# H2AR32.net
KiCad netlist of a schematic drawn in EAGLE
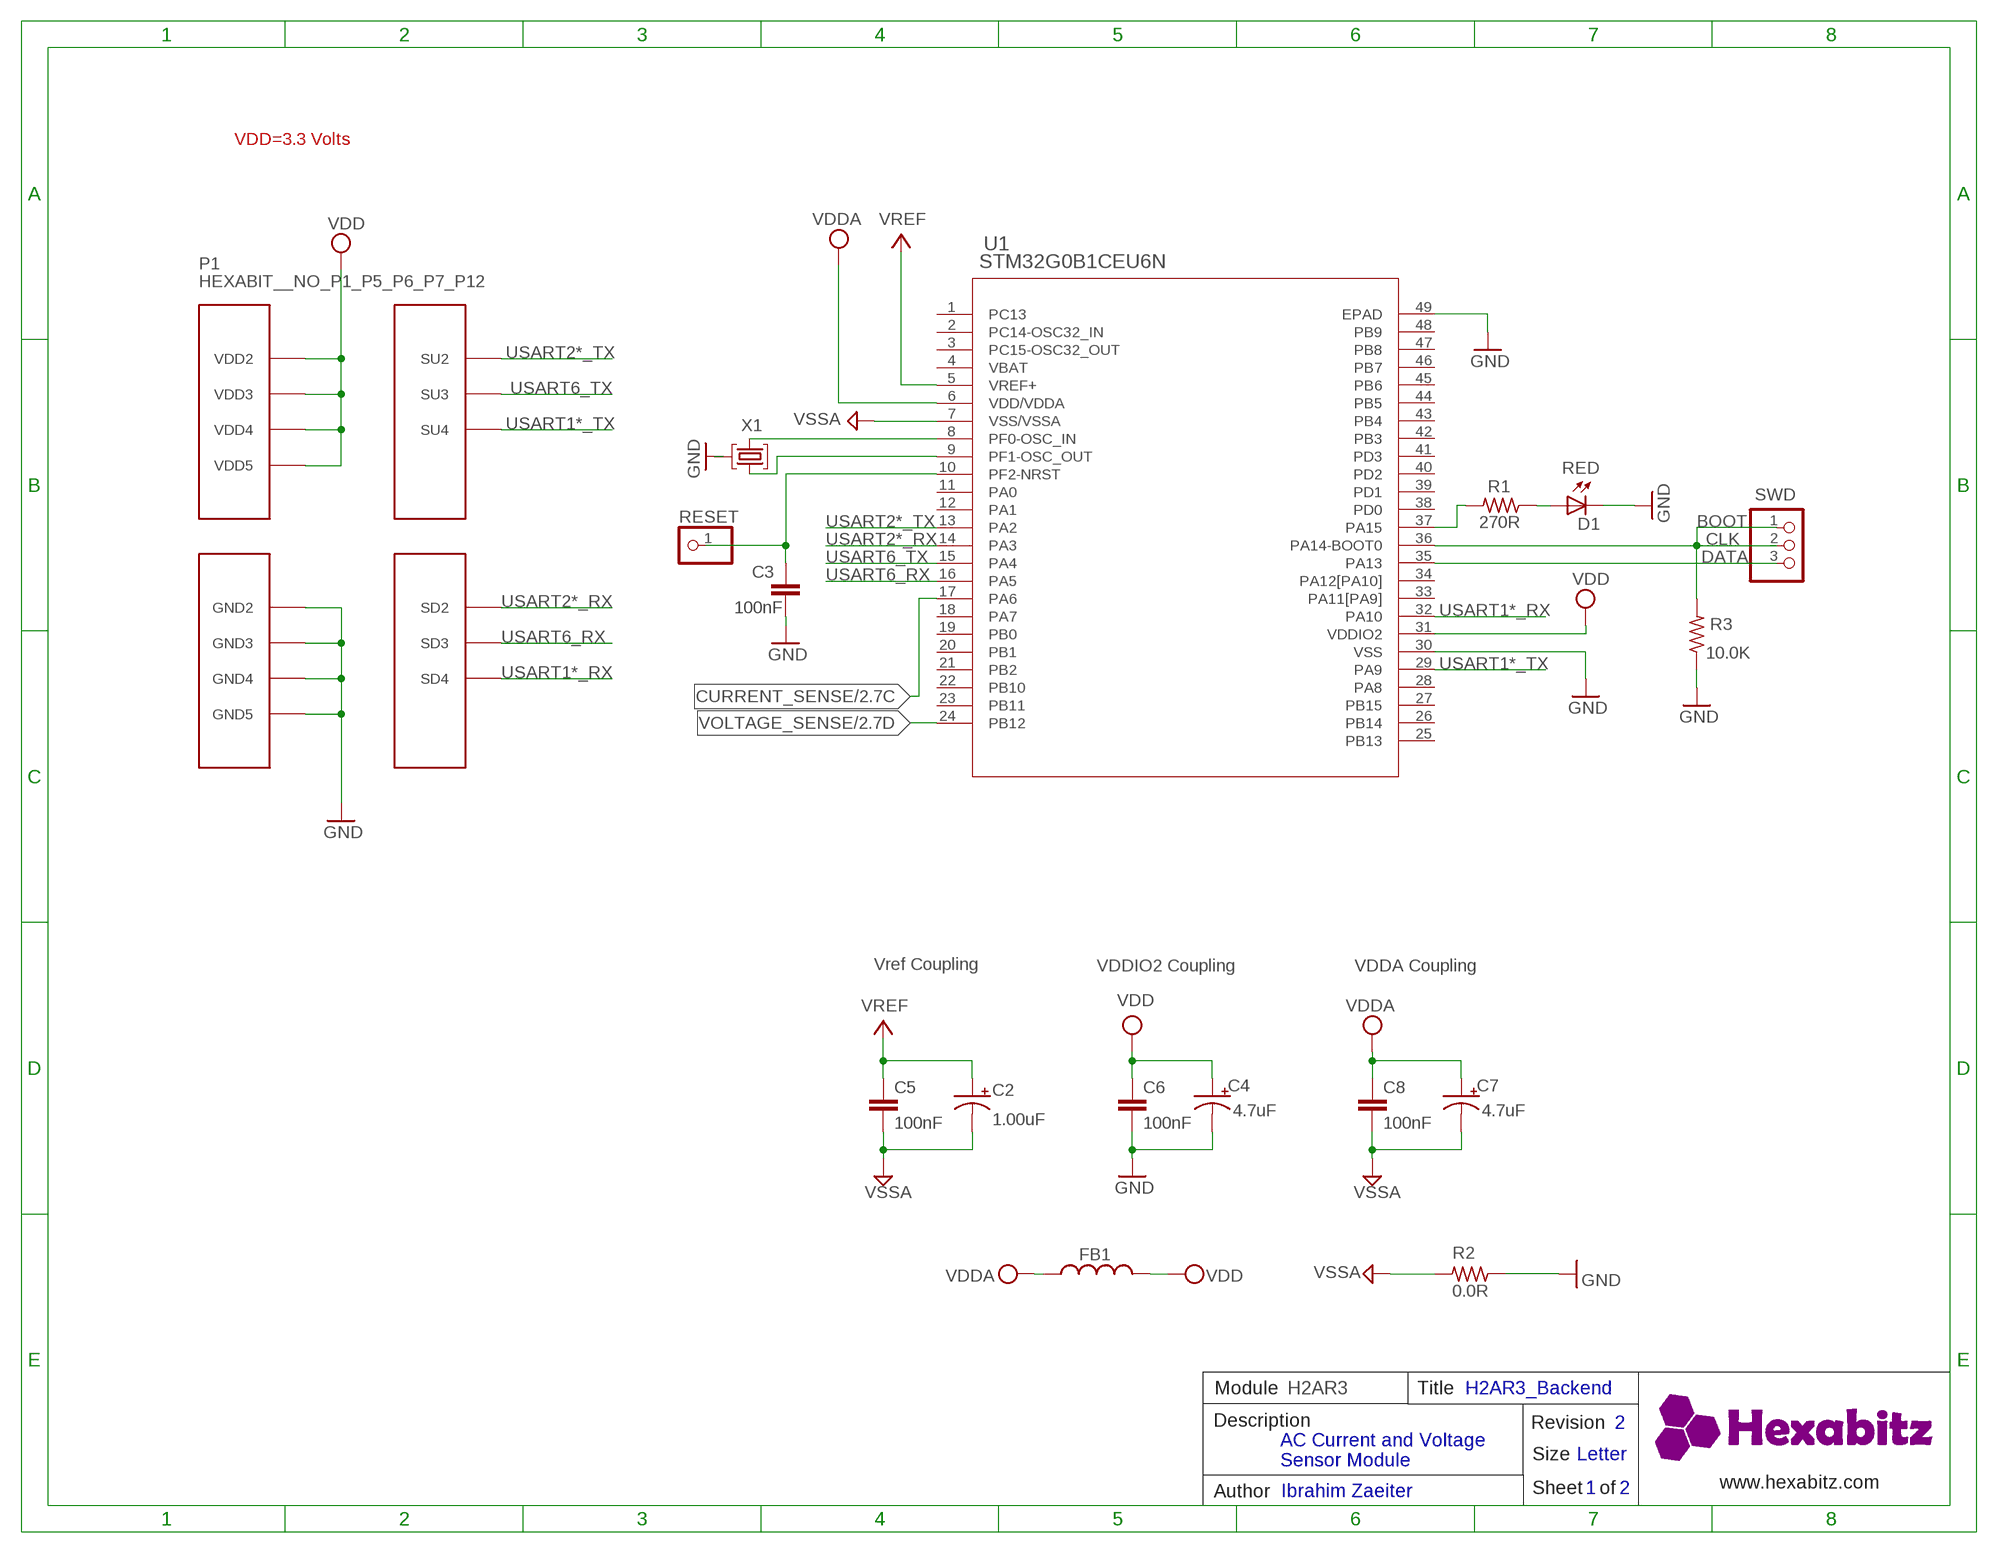
[diagram p0: schematic, sheet 1]
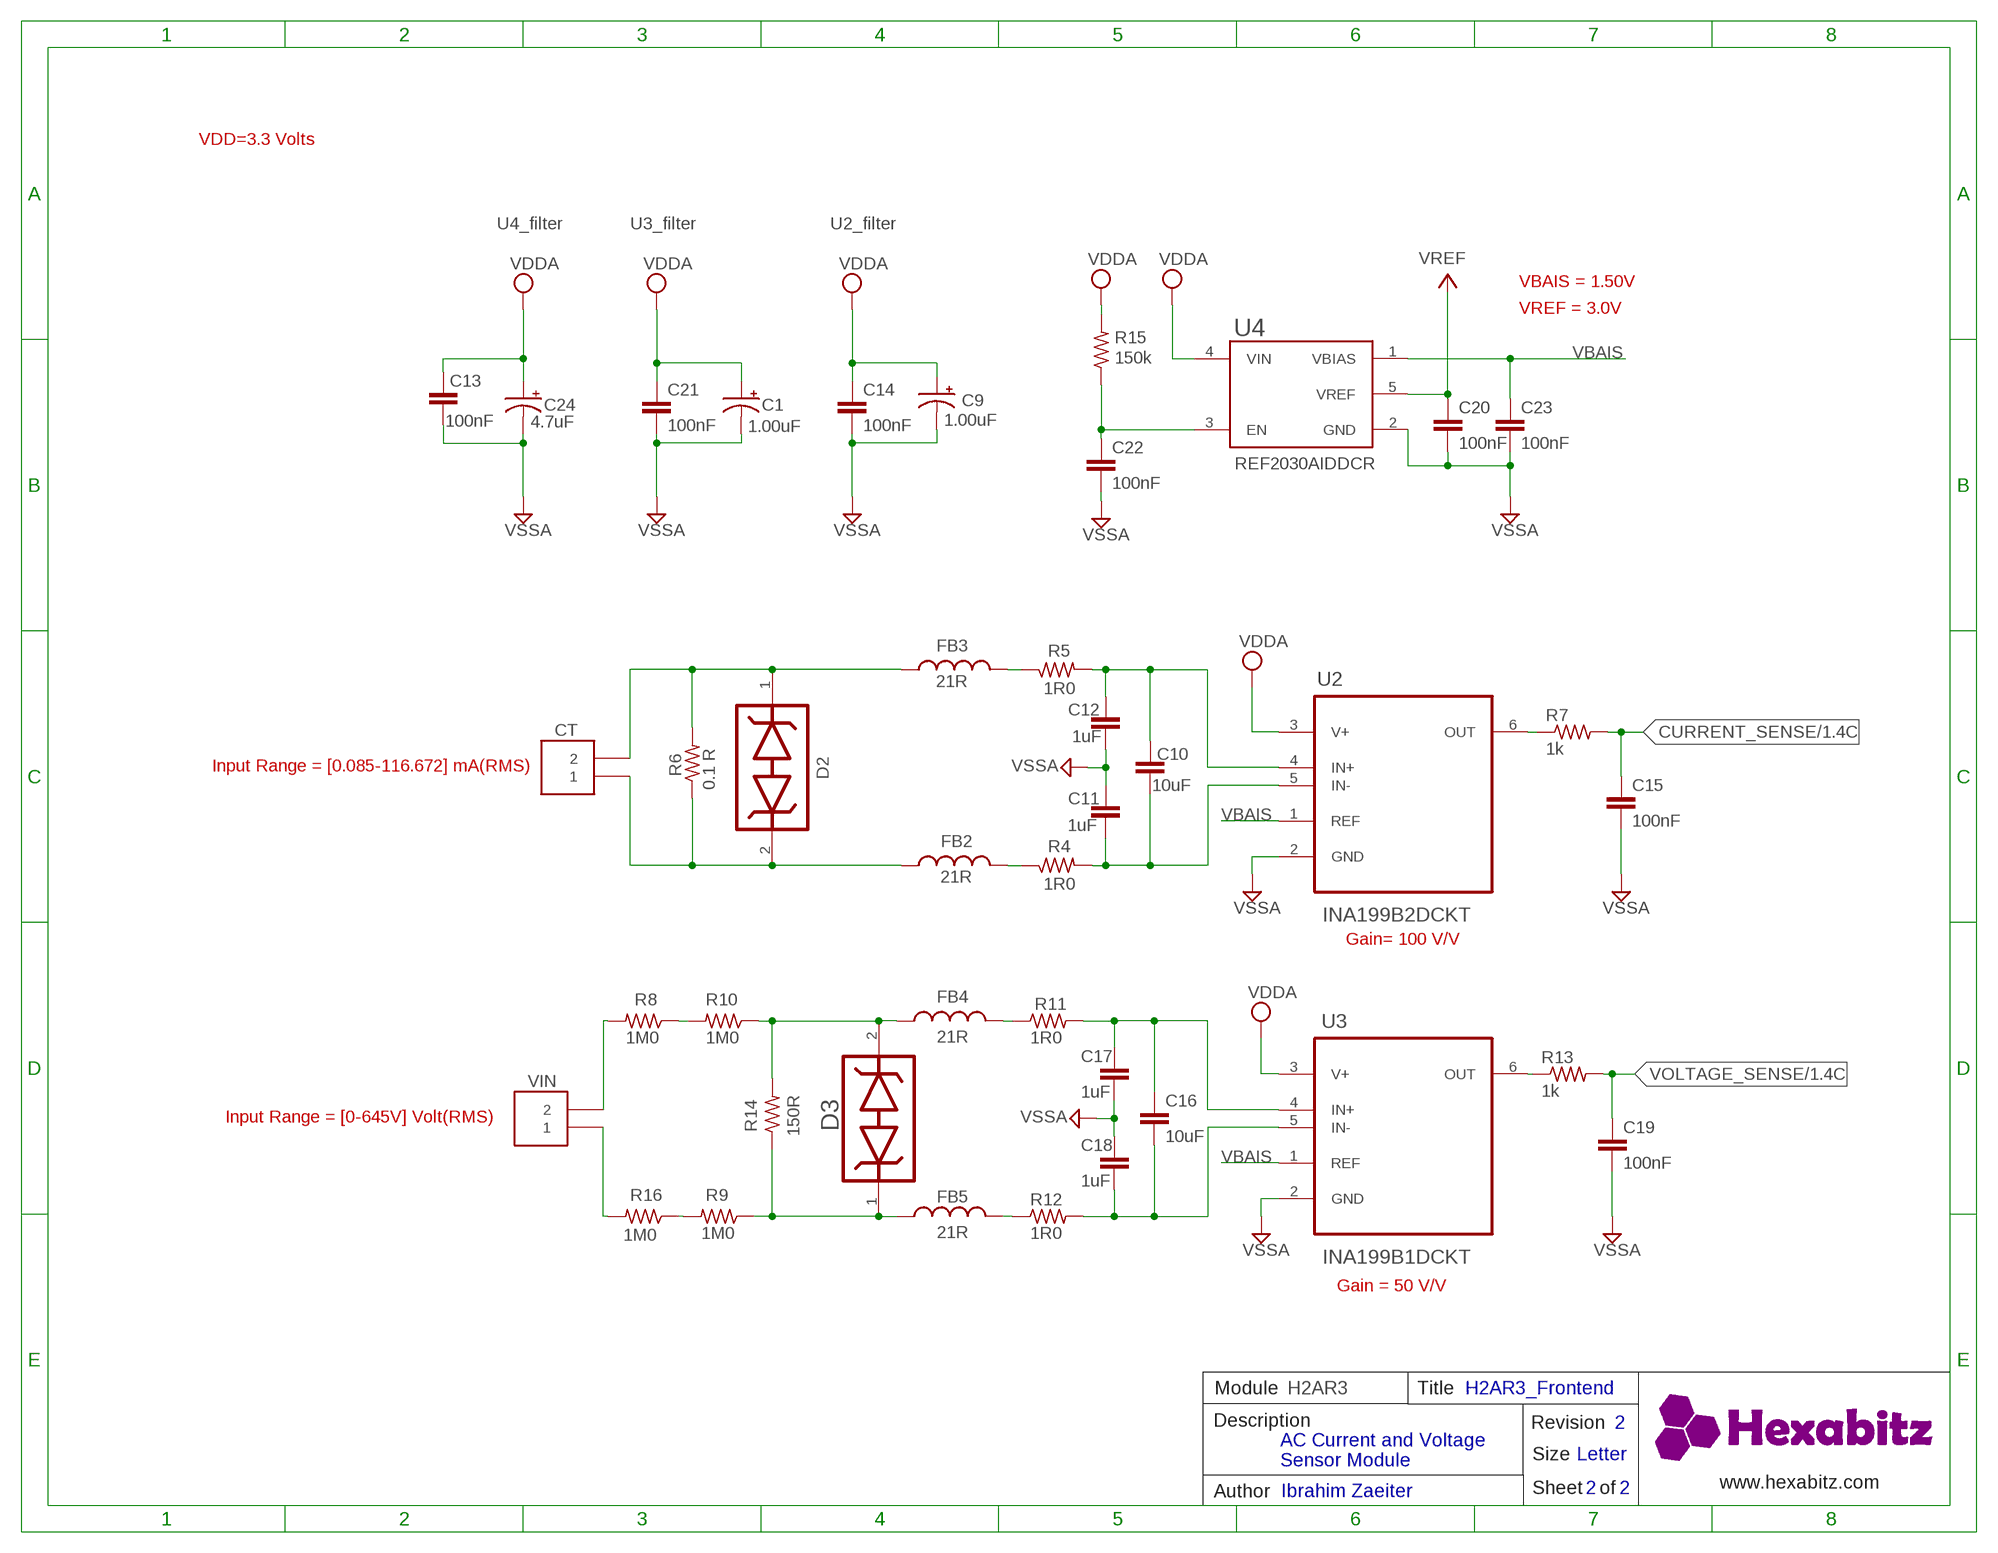
[diagram p1: schematic, sheet 2]

(export (version "E")
  (design (tool "Eeschema 10.0.6"))
  (components
    (comp (ref "C1")
      (value "1.00uF")
      (footprint "eagle-import:C-0805-POL")
      (fields
        (field (name "CAPACITANCE") "1.00uF")
        (field (name "MFN") "Yageo")
        (field (name "MPN") "CC0805KKX7R7BB105")
        (field (name "OCTOPART_URL") "https://octopart.com/cc0805kkx7r7bb105-yageo-8376555?r=sp&s=YKl1wwtkROau_X5nniH2ig")
        (field (name "TOLERANCE") "10%")
        (field (name "VOLTAGE_RATING") "16V")
      )
      (libsource (lib "eagle-import") (part "C-0805-POL"))
    )
    (comp (ref "C9")
      (value "1.00uF")
      (footprint "eagle-import:C-0805-POL")
      (fields
        (field (name "CAPACITANCE") "1.00uF")
        (field (name "MFN") "Yageo")
        (field (name "MPN") "CC0805KKX7R7BB105")
        (field (name "OCTOPART_URL") "https://octopart.com/cc0805kkx7r7bb105-yageo-8376555?r=sp&s=YKl1wwtkROau_X5nniH2ig")
        (field (name "TOLERANCE") "10%")
        (field (name "VOLTAGE_RATING") "16V")
      )
      (libsource (lib "eagle-import") (part "C-0805-POL"))
    )
    (comp (ref "C10")
      (value "10uF")
      (footprint "eagle-import:C-0603")
      (fields
        (field (name "CAPACITANCE") "10uF")
        (field (name "MFN") "KEMET")
        (field (name "MPN") "C0603C106M9PACTU")
        (field (name "OCTOPART_URL") "https://octopart.com/c0603c106m9pactu-kemet-8375727?r=sp")
        (field (name "VOLTAGE_RATING") "6.3v")
      )
      (libsource (lib "eagle-import") (part "C-0603"))
    )
    (comp (ref "C11")
      (value "1uF")
      (footprint "eagle-import:C-0603")
      (fields
        (field (name "CAPACITANCE") "1uF")
        (field (name "MFN") "KEMET")
        (field (name "MPN") "C0603C105K8RACTU")
        (field (name "OCTOPART_URL") "https://octopart.com/c0603c105k8ractu-kemet-12595642?r=sp")
        (field (name "TOLERANCE") "10%")
        (field (name "VOLTAGE_RATING") "10v")
      )
      (libsource (lib "eagle-import") (part "C-0603"))
    )
    (comp (ref "C12")
      (value "1uF")
      (footprint "eagle-import:C-0603")
      (fields
        (field (name "CAPACITANCE") "1uF")
        (field (name "MFN") "KEMET")
        (field (name "MPN") "C0603C105K8RACTU")
        (field (name "OCTOPART_URL") "https://octopart.com/c0603c105k8ractu-kemet-12595642?r=sp")
        (field (name "TOLERANCE") "10%")
        (field (name "VOLTAGE_RATING") "10v")
      )
      (libsource (lib "eagle-import") (part "C-0603"))
    )
    (comp (ref "C13")
      (value "100nF")
      (footprint "eagle-import:C-0603")
      (fields
        (field (name "CAPACITANCE") "100nF")
        (field (name "MFN") "KEMET")
        (field (name "MPN") "C0603C104K8RACTU")
        (field (name "OCTOPART_URL") "https://octopart.com/c0603c104k8ractu-kemet-145075?r=sp&s=9bS9ASSwSEqMCE9KBEQZ0g")
        (field (name "TOLERANCE") "10%")
        (field (name "VOLTAGE_RATING") "10V")
      )
      (libsource (lib "eagle-import") (part "C-0603"))
    )
    (comp (ref "C14")
      (value "100nF")
      (footprint "eagle-import:C-0603")
      (fields
        (field (name "CAPACITANCE") "100nF")
        (field (name "MFN") "KEMET")
        (field (name "MPN") "C0603C104K8RACTU")
        (field (name "OCTOPART_URL") "https://octopart.com/c0603c104k8ractu-kemet-145075?r=sp&s=9bS9ASSwSEqMCE9KBEQZ0g")
        (field (name "TOLERANCE") "10%")
        (field (name "VOLTAGE_RATING") "10V")
      )
      (libsource (lib "eagle-import") (part "C-0603"))
    )
    (comp (ref "C15")
      (value "100nF")
      (footprint "eagle-import:C-0603")
      (fields
        (field (name "CAPACITANCE") "100nF")
        (field (name "MFN") "KEMET")
        (field (name "MPN") "C0603C104K8RACTU")
        (field (name "OCTOPART_URL") "https://octopart.com/c0603c104k8ractu-kemet-145075?r=sp&s=9bS9ASSwSEqMCE9KBEQZ0g")
        (field (name "TOLERANCE") "10%")
        (field (name "VOLTAGE_RATING") "10V")
      )
      (libsource (lib "eagle-import") (part "C-0603"))
    )
    (comp (ref "C16")
      (value "10uF")
      (footprint "eagle-import:C-0603")
      (fields
        (field (name "CAPACITANCE") "10uF")
        (field (name "MFN") "KEMET")
        (field (name "MPN") "C0603C106M9PACTU")
        (field (name "OCTOPART_URL") "https://octopart.com/c0603c106m9pactu-kemet-8375727?r=sp")
        (field (name "TOLERANCE") "20%")
        (field (name "VOLTAGE_RATING") "6.3V")
      )
      (libsource (lib "eagle-import") (part "C-0603"))
    )
    (comp (ref "C17")
      (value "1uF")
      (footprint "eagle-import:C-0603")
      (fields
        (field (name "CAPACITANCE") "1uF")
        (field (name "MFN") "KEMET")
        (field (name "MPN") "C0603C105K8RACTU")
        (field (name "OCTOPART_URL") "https://octopart.com/c0603c105k8ractu-kemet-12595642?r=sp")
        (field (name "TOLERANCE") "10%")
        (field (name "VOLTAGE_RATING") "10v")
      )
      (libsource (lib "eagle-import") (part "C-0603"))
    )
    (comp (ref "C18")
      (value "1uF")
      (footprint "eagle-import:C-0603")
      (fields
        (field (name "CAPACITANCE") "1uF")
        (field (name "MFN") "KEMET")
        (field (name "MPN") "C0603C105K8RACTU")
        (field (name "OCTOPART_URL") "https://octopart.com/c0603c105k8ractu-kemet-12595642?r=sp")
        (field (name "TOLERANCE") "10%")
        (field (name "VOLTAGE_RATING") "10v")
      )
      (libsource (lib "eagle-import") (part "C-0603"))
    )
    (comp (ref "C19")
      (value "100nF")
      (footprint "eagle-import:C-0603")
      (fields
        (field (name "CAPACITANCE") "100nF")
        (field (name "MFN") "KEMET")
        (field (name "MPN") "C0603C104K8RACTU")
        (field (name "OCTOPART_URL") "https://octopart.com/c0603c104k8ractu-kemet-145075?r=sp&s=9bS9ASSwSEqMCE9KBEQZ0g")
        (field (name "TOLERANCE") "10%")
        (field (name "VOLTAGE_RATING") "10V")
      )
      (libsource (lib "eagle-import") (part "C-0603"))
    )
    (comp (ref "C20")
      (value "100nF")
      (footprint "eagle-import:C-0603")
      (fields
        (field (name "CAPACITANCE") "100nF")
        (field (name "MFN") "KEMET")
        (field (name "MPN") "C0603C104K8RACTU")
        (field (name "OCTOPART_URL") "https://octopart.com/c0603c104k8ractu-kemet-145075?r=sp&s=9bS9ASSwSEqMCE9KBEQZ0g")
        (field (name "TOLERANCE") "10%")
        (field (name "VOLTAGE_RATING") "10V")
      )
      (libsource (lib "eagle-import") (part "C-0603"))
    )
    (comp (ref "C21")
      (value "100nF")
      (footprint "eagle-import:C-0603")
      (fields
        (field (name "CAPACITANCE") "100nF")
        (field (name "MFN") "KEMET")
        (field (name "MPN") "C0603C104K8RACTU")
        (field (name "OCTOPART_URL") "https://octopart.com/c0603c104k8ractu-kemet-145075?r=sp&s=9bS9ASSwSEqMCE9KBEQZ0g")
        (field (name "TOLERANCE") "10%")
        (field (name "VOLTAGE_RATING") "10V")
      )
      (libsource (lib "eagle-import") (part "C-0603"))
    )
    (comp (ref "C22")
      (value "100nF")
      (footprint "eagle-import:C-0603")
      (fields
        (field (name "CAPACITANCE") "100nF")
        (field (name "MFN") "KEMET")
        (field (name "MPN") "C0603C104K8RACTU")
        (field (name "OCTOPART_URL") "https://octopart.com/c0603c104k8ractu-kemet-145075?r=sp&s=9bS9ASSwSEqMCE9KBEQZ0g")
        (field (name "TOLERANCE") "10%")
        (field (name "VOLTAGE_RATING") "10V")
      )
      (libsource (lib "eagle-import") (part "C-0603"))
    )
    (comp (ref "C23")
      (value "100nF")
      (footprint "eagle-import:C-0603")
      (fields
        (field (name "CAPACITANCE") "100nF")
        (field (name "MFN") "KEMET")
        (field (name "MPN") "C0603C104K8RACTU")
        (field (name "OCTOPART_URL") "https://octopart.com/c0603c104k8ractu-kemet-145075?r=sp&s=9bS9ASSwSEqMCE9KBEQZ0g")
        (field (name "TOLERANCE") "10%")
        (field (name "VOLTAGE_RATING") "10V")
      )
      (libsource (lib "eagle-import") (part "C-0603"))
    )
    (comp (ref "C24")
      (value "4.7uF")
      (footprint "eagle-import:C-0805-POL")
      (fields
        (field (name "CAPACITANCE") "4.7uF")
        (field (name "MFN") "Murata")
        (field (name "MPN") "GRM21BC81E475KA12L")
        (field (name "OCTOPART_URL") "https://octopart.com/grm21bc81e475ka12l-murata-10331911?r=sp&s=RY3qZSD8T6mG6TC9CHI5qQ")
        (field (name "TOLERANCE") "10%")
        (field (name "VOLTAGE_RATING") "25V")
      )
      (libsource (lib "eagle-import") (part "C-0805-POL"))
    )
    (comp (ref "CT")
      (value "1546111-2")
      (footprint "eagle-import:1546111-2")
      (libsource (lib "eagle-import") (part "1546111-2"))
    )
    (comp (ref "D2")
      (value "BOURNS_CDSOD323-T03SCBOURNS_CDSOD323-T03SC_0_0")
      (footprint "eagle-import:BOURNS_CDSOD323-T03SC_0")
      (fields (field (name "MPN") "CDSOD323-T03SC"))
      (libsource (lib "eagle-import") (part "BOURNS_CDSOD323-T03SCBOURNS_CDSOD323-T03SC_0_0"))
    )
    (comp (ref "D3")
      (value "BOURNS_CDSOD323-T03SCBOURNS_CDSOD323-T03SC_0_0")
      (footprint "eagle-import:BOURNS_CDSOD323-T03SC_0")
      (fields (field (name "MPN") "CDSOD323-T03SC"))
      (libsource (lib "eagle-import") (part "BOURNS_CDSOD323-T03SCBOURNS_CDSOD323-T03SC_0_0"))
    )
    (comp (ref "FB2")
      (value "21R")
      (footprint "eagle-import:FB-0805")
      (fields
        (field (name "MFN") "Taiyo Yuden")
        (field (name "MPN") "FBMJ2125HM210NT")
        (field (name "OCTOPART_URL") "https://octopart.com/fbmj2125hm210nt-taiyo+yuden-368424?r=sp")
      )
      (libsource (lib "eagle-import") (part "FB-0805"))
    )
    (comp (ref "FB3")
      (value "21R")
      (footprint "eagle-import:FB-0805")
      (fields
        (field (name "MFN") "Taiyo Yuden")
        (field (name "MPN") "FBMJ2125HM210NT")
        (field (name "OCTOPART_URL") "https://octopart.com/fbmj2125hm210nt-taiyo+yuden-368424?r=sp")
      )
      (libsource (lib "eagle-import") (part "FB-0805"))
    )
    (comp (ref "FB4")
      (value "21R")
      (footprint "eagle-import:FB-0805")
      (fields
        (field (name "MFN") "Taiyo Yuden")
        (field (name "MPN") "FBMJ2125HM210NT")
        (field (name "OCTOPART_URL") "https://octopart.com/fbmj2125hm210nt-taiyo+yuden-368424?r=sp")
      )
      (libsource (lib "eagle-import") (part "FB-0805"))
    )
    (comp (ref "FB5")
      (value "21R")
      (footprint "eagle-import:FB-0805")
      (fields
        (field (name "MFN") "Taiyo Yuden")
        (field (name "MPN") "FBMJ2125HM210NT")
        (field (name "OCTOPART_URL") "https://octopart.com/fbmj2125hm210nt-taiyo+yuden-368424?r=sp")
      )
      (libsource (lib "eagle-import") (part "FB-0805"))
    )
    (comp (ref "R4")
      (value "1R0")
      (footprint "eagle-import:R-0603")
      (fields
        (field (name "MFN") "Vishay")
        (field (name "MPN") "CRCW06031R00FKEA")
        (field (name "OCTOPART_URL") "https://octopart.com/crcw06031r00fkea-vishay-39713722?r=sp&s=biXSlGylTBiwPOCcABx_kA")
        (field (name "RESISTANCE") "1")
        (field (name "TOLERANCE") "1%")
      )
      (libsource (lib "eagle-import") (part "R-0603"))
    )
    (comp (ref "R5")
      (value "1R0")
      (footprint "eagle-import:R-0603")
      (fields
        (field (name "MFN") "Vishay")
        (field (name "MPN") "CRCW06031R00FKEA")
        (field (name "OCTOPART_URL") "https://octopart.com/crcw06031r00fkea-vishay-39713722?r=sp&s=biXSlGylTBiwPOCcABx_kA")
        (field (name "RESISTANCE") "1")
        (field (name "TOLERANCE") "1%")
      )
      (libsource (lib "eagle-import") (part "R-0603"))
    )
    (comp (ref "R6")
      (value "0.1 R")
      (footprint "eagle-import:R2512")
      (libsource (lib "eagle-import") (part "R-US_R2512"))
    )
    (comp (ref "R7")
      (value "1k")
      (footprint "eagle-import:R-0603")
      (fields
        (field (name "MFN") "Yageo")
        (field (name "MPN") "RC0603JR-071KL")
        (field (name "OCTOPART_URL") "https://octopart.com/rc0603jr-071kl-yageo-55402888?r=sp")
        (field (name "RESISTANCE") "1K")
        (field (name "TOLERANCE") "5%")
      )
      (libsource (lib "eagle-import") (part "R-0603"))
    )
    (comp (ref "R8")
      (value "1M0")
      (footprint "eagle-import:R1206")
      (fields
        (field (name "MPN") "RNCF2512BTE1M10")
        (field (name "MFN") "Yageo")
        (field (name "MPN_1") "RT1206BRD071ML")
        (field (name "OCTOPART_URL") "https://octopart.com/rt1206brd071ml-yageo-1262221?r=sp")
      )
      (libsource (lib "eagle-import") (part "R_1206R1206"))
    )
    (comp (ref "R9")
      (value "1M0")
      (footprint "eagle-import:R1206")
      (fields
        (field (name "MPN") "RNCF2512BTE1M10")
        (field (name "MFN") "Yageo")
        (field (name "MPN_1") "RT1206BRD071ML")
        (field (name "OCTOPART_URL") "https://octopart.com/rt1206brd071ml-yageo-1262221?r=sp")
      )
      (libsource (lib "eagle-import") (part "R_1206R1206"))
    )
    (comp (ref "R10")
      (value "1M0")
      (footprint "eagle-import:R1206")
      (fields
        (field (name "MPN") "RNCF2512BTE1M10")
        (field (name "MFN") "Yageo")
        (field (name "MPN_1") "RT1206BRD071ML")
        (field (name "OCTOPART_URL") "https://octopart.com/rt1206brd071ml-yageo-1262221?r=sp")
      )
      (libsource (lib "eagle-import") (part "R_1206R1206"))
    )
    (comp (ref "R11")
      (value "1R0")
      (footprint "eagle-import:R-0603")
      (fields
        (field (name "MFN") "Vishay")
        (field (name "MPN") "CRCW06031R00FKEA")
        (field (name "OCTOPART_URL") "https://octopart.com/crcw06031r00fkea-vishay-39713722?r=sp&s=biXSlGylTBiwPOCcABx_kA")
        (field (name "RESISTANCE") "1")
        (field (name "TOLERANCE") "1%")
      )
      (libsource (lib "eagle-import") (part "R-0603"))
    )
    (comp (ref "R12")
      (value "1R0")
      (footprint "eagle-import:R-0603")
      (fields
        (field (name "MFN") "Vishay")
        (field (name "MPN") "CRCW06031R00FKEA")
        (field (name "OCTOPART_URL") "https://octopart.com/crcw06031r00fkea-vishay-39713722?r=sp&s=biXSlGylTBiwPOCcABx_kA")
        (field (name "RESISTANCE") "1")
        (field (name "TOLERANCE") "1%")
      )
      (libsource (lib "eagle-import") (part "R-0603"))
    )
    (comp (ref "R13")
      (value "1k")
      (footprint "eagle-import:R-0603")
      (fields
        (field (name "MFN") "Yageo")
        (field (name "MPN") "RC0603JR-071KL")
        (field (name "OCTOPART_URL") "https://octopart.com/rc0603jr-071kl-yageo-55402888?r=sp")
        (field (name "RESISTANCE") "1K")
        (field (name "TOLERANCE") "5%")
      )
      (libsource (lib "eagle-import") (part "R-0603"))
    )
    (comp (ref "R14")
      (value "150R")
      (footprint "eagle-import:R1206")
      (fields
        (field (name "MPN") "RNCF2512BTE1M10")
        (field (name "MFN") "Panasonic")
        (field (name "MPN_1") "ERA-8AEB151V")
        (field (name "OCTOPART_URL") "https://octopart.com/era-8aeb151v-panasonic-55477439?r=sp")
      )
      (libsource (lib "eagle-import") (part "R_1206R1206"))
    )
    (comp (ref "R15")
      (value "150k")
      (footprint "eagle-import:R-0603")
      (fields
        (field (name "MFN") "Vishay")
        (field (name "MPN") "CRCW0603150KFKEA")
        (field (name "OCTOPART_URL") "https://octopart.com/crcw0603150kfkea-vishay-39455816?r=sp")
        (field (name "RESISTANCE") "150K")
        (field (name "TOLERANCE") "1%")
      )
      (libsource (lib "eagle-import") (part "R-0603"))
    )
    (comp (ref "R16")
      (value "1M0")
      (footprint "eagle-import:R1206")
      (fields
        (field (name "MPN") "RNCF2512BTE1M10")
        (field (name "MFN") "Yageo")
        (field (name "MPN_1") "RT1206BRD071ML")
        (field (name "OCTOPART_URL") "https://octopart.com/rt1206brd071ml-yageo-1262221?r=sp")
      )
      (libsource (lib "eagle-import") (part "R_1206R1206"))
    )
    (comp (ref "U2")
      (value "INA199B2DCKT")
      (footprint "eagle-import:SOT65P210X110-6N")
      (libsource (lib "eagle-import") (part "INA199B2DCKT"))
    )
    (comp (ref "U3")
      (value "INA199B1DCKT")
      (footprint "eagle-import:SOT65P210X110-6N")
      (libsource (lib "eagle-import") (part "INA199B1DCKT"))
    )
    (comp (ref "U4")
      (value "TEXAS_INSTRUMENTS_REF2033AIDDCRTEXAS_INSTRUMENTS_REF2033AIDDCR_0_2")
      (footprint "eagle-import:TEXAS_INSTRUMENTS_REF2033AIDDCR_2")
      (fields (field (name "MPN") "REF2033AIDDCR") (field (name "MPN_1") "REF2030AIDDCR"))
      (libsource (lib "eagle-import") (part "TEXAS_INSTRUMENTS_REF2033AIDDCRTEXAS_INSTRUMENTS_REF2033AIDDCR_0_2"))
    )
    (comp (ref "VIN")
      (value "1546111-2")
      (footprint "eagle-import:1546111-2")
      (libsource (lib "eagle-import") (part "1546111-2"))
    )
    (comp (ref "C2")
      (value "1.00uF")
      (footprint "eagle-import:C-0805-POL")
      (fields
        (field (name "CAPACITANCE") "1.00uF")
        (field (name "MFN") "Yageo")
        (field (name "MPN") "CC0805KKX7R7BB105")
        (field (name "OCTOPART_URL") "https://octopart.com/cc0805kkx7r7bb105-yageo-8376555?r=sp&s=YKl1wwtkROau_X5nniH2ig")
        (field (name "TOLERANCE") "10%")
        (field (name "VOLTAGE_RATING") "16V")
      )
      (libsource (lib "eagle-import") (part "C-0805-POL"))
    )
    (comp (ref "C3")
      (value "100nF")
      (footprint "eagle-import:C-0603")
      (fields
        (field (name "CAPACITANCE") "100nF")
        (field (name "MFN") "KEMET")
        (field (name "MPN") "C0603C104K8RACTU")
        (field (name "OCTOPART_URL") "https://octopart.com/c0603c104k8ractu-kemet-145075?r=sp&s=9bS9ASSwSEqMCE9KBEQZ0g")
        (field (name "TOLERANCE") "10%")
        (field (name "VOLTAGE_RATING") "10V")
      )
      (libsource (lib "eagle-import") (part "C-0603"))
    )
    (comp (ref "C4")
      (value "4.7uF")
      (footprint "eagle-import:C-0805-POL")
      (fields
        (field (name "CAPACITANCE") "4.7uF")
        (field (name "MFN") "Murata")
        (field (name "MPN") "GRM21BC81E475KA12L")
        (field (name "OCTOPART_URL") "https://octopart.com/grm21bc81e475ka12l-murata-10331911?r=sp&s=RY3qZSD8T6mG6TC9CHI5qQ")
        (field (name "TOLERANCE") "10%")
        (field (name "VOLTAGE_RATING") "25V")
      )
      (libsource (lib "eagle-import") (part "C-0805-POL"))
    )
    (comp (ref "C5")
      (value "100nF")
      (footprint "eagle-import:C-0603")
      (fields
        (field (name "CAPACITANCE") "100nF")
        (field (name "MFN") "KEMET")
        (field (name "MPN") "C0603C104K8RACTU")
        (field (name "OCTOPART_URL") "https://octopart.com/c0603c104k8ractu-kemet-145075?r=sp&s=9bS9ASSwSEqMCE9KBEQZ0g")
        (field (name "TOLERANCE") "10%")
        (field (name "VOLTAGE_RATING") "10V")
      )
      (libsource (lib "eagle-import") (part "C-0603"))
    )
    (comp (ref "C6")
      (value "100nF")
      (footprint "eagle-import:C-0603")
      (fields
        (field (name "CAPACITANCE") "100nF")
        (field (name "MFN") "KEMET")
        (field (name "MPN") "C0603C104K8RACTU")
        (field (name "OCTOPART_URL") "https://octopart.com/c0603c104k8ractu-kemet-145075?r=sp&s=9bS9ASSwSEqMCE9KBEQZ0g")
        (field (name "TOLERANCE") "10%")
        (field (name "VOLTAGE_RATING") "10V")
      )
      (libsource (lib "eagle-import") (part "C-0603"))
    )
    (comp (ref "C7")
      (value "4.7uF")
      (footprint "eagle-import:C-0805-POL")
      (fields
        (field (name "CAPACITANCE") "4.7uF")
        (field (name "MFN") "Murata")
        (field (name "MPN") "GRM21BC81E475KA12L")
        (field (name "OCTOPART_URL") "https://octopart.com/grm21bc81e475ka12l-murata-10331911?r=sp&s=RY3qZSD8T6mG6TC9CHI5qQ")
        (field (name "TOLERANCE") "10%")
        (field (name "VOLTAGE_RATING") "25V")
      )
      (libsource (lib "eagle-import") (part "C-0805-POL"))
    )
    (comp (ref "C8")
      (value "100nF")
      (footprint "eagle-import:C-0603")
      (fields
        (field (name "CAPACITANCE") "100nF")
        (field (name "MFN") "KEMET")
        (field (name "MPN") "C0603C104K8RACTU")
        (field (name "OCTOPART_URL") "https://octopart.com/c0603c104k8ractu-kemet-145075?r=sp&s=9bS9ASSwSEqMCE9KBEQZ0g")
        (field (name "TOLERANCE") "10%")
        (field (name "VOLTAGE_RATING") "10")
      )
      (libsource (lib "eagle-import") (part "C-0603"))
    )
    (comp (ref "D1")
      (value "RED")
      (footprint "eagle-import:VLMS1300-GS08")
      (fields
        (field (name "MPN") "VLMS1300-GS08")
        (field (name "MFN") "Vishay")
        (field (name "MPN_1") "VLMS1300-GS08")
        (field (name "OCTOPART_URL") "https://octopart.com/vlms1300-gs08-vishay-21709201?r=sp&s=_gcP4_q8T1SC6PJQPTQ9yA")
      )
      (libsource (lib "eagle-import") (part "VLMS1300-GS08"))
    )
    (comp (ref "FB1")
      (value "FB-TDK_MMZ1608Y300B")
      (footprint "eagle-import:FB-TDK_MMZ1608Y300B")
      (fields
        (field (name "MFN") "TDK ")
        (field (name "MPN") "MMZ1608Y300B")
        (field (name "OCTOPART_URL") "https://octopart.com/mmz1608y300b-tdk-368280?r=sp&s=cd9_2ZEqQ9q9UNBuQgHAiA")
      )
      (libsource (lib "eagle-import") (part "FB-TDK_MMZ1608Y300B"))
    )
    (comp (ref "P1")
      (value "HEXABIT__NO_P1_P5_P6_P7_P12")
      (footprint "eagle-import:HEXABIT_17.32_NO_P1_P6_P5_P7_P12")
      (libsource (lib "eagle-import") (part "HEXABIT_?_NO_P1_P5_P6_P7_P12"))
    )
    (comp (ref "R1")
      (value "270R")
      (footprint "eagle-import:R-0603")
      (fields
        (field (name "MFN") "Yageo")
        (field (name "MPN") "RC0603FR-07270RL")
        (field (name "OCTOPART_URL") "https://octopart.com/search?q=RC0603FR-07270RL&start=0")
        (field (name "RESISTANCE") "270.0 Ohm")
        (field (name "TOLERANCE") "5%")
      )
      (libsource (lib "eagle-import") (part "R-0603"))
    )
    (comp (ref "R2")
      (value "0.0R")
      (footprint "eagle-import:R-0603")
      (fields
        (field (name "MFN") "Yageo")
        (field (name "MPN") "RC0603JR-070RL")
        (field (name "OCTOPART_URL") "https://octopart.com/rc0603jr-070rl-yageo-1241539?r=sp&s=X2NteqRjRNWrnx42Y0aliA")
        (field (name "RESISTANCE") "0.0 Ohm")
      )
      (libsource (lib "eagle-import") (part "R-0603"))
    )
    (comp (ref "R3")
      (value "10.0K")
      (footprint "eagle-import:R-0603")
      (fields
        (field (name "MFN") "Yageo")
        (field (name "MPN") "RC0603JR-0710KL")
        (field (name "OCTOPART_URL") "https://octopart.com/search?q=RC0603JR-0710KL&start=0")
        (field (name "RESISTANCE") "10.0K Ohm")
        (field (name "TOLERANCE") "5%")
      )
      (libsource (lib "eagle-import") (part "R-0603"))
    )
    (comp (ref "RESET")
      (value "R")
      (footprint "eagle-import:1X01")
      (fields (field (name "MPN") "87227-1"))
      (libsource (lib "eagle-import") (part "PINHD-1X1"))
    )
    (comp (ref "SWD")
      (value "PINHD-1X3")
      (footprint "eagle-import:1X03")
      (libsource (lib "eagle-import") (part "PINHD-1X3"))
    )
    (comp (ref "U1")
      (value "STM32G0B1CEU6N")
      (footprint "eagle-import:HEXABITZ_ICS_QFN_B1CEU6_STM-L")
      (libsource (lib "eagle-import") (part "STM32G0B1CEU6N"))
    )
    (comp (ref "X1")
      (value "XTALL_CSTCE8M00G52")
      (footprint "eagle-import:XTALL_CSTCE8M00G52")
      (fields (field (name "MPN") "CSTCE8M00G52Z-R0"))
      (libsource (lib "eagle-import") (part "XTALL_CSTCE8M00G52"))
    )
  )
  (nets
    (net (code "1") (name "CLK") (class "Default")
      (node (ref "R3") (pin "2") (pinfunction "2_2") (pintype "passive"))
      (node (ref "SWD") (pin "1") (pinfunction "1_1") (pintype "passive"))
      (node (ref "SWD") (pin "2") (pinfunction "2_2") (pintype "passive"))
      (node (ref "U1") (pin "36") (pinfunction "PA14-BOOT0_36") (pintype "bidirectional"))
    )
    (net (code "2") (name "CURRENT_SENSE") (class "Default")
      (node (ref "C15") (pin "1") (pinfunction "1_1") (pintype "passive"))
      (node (ref "R7") (pin "2") (pinfunction "2_2") (pintype "passive"))
      (node (ref "U1") (pin "17") (pinfunction "PA6_17") (pintype "bidirectional"))
    )
    (net (code "3") (name "DATA") (class "Default")
      (node (ref "SWD") (pin "3") (pinfunction "3_3") (pintype "passive"))
      (node (ref "U1") (pin "35") (pinfunction "PA13_35") (pintype "bidirectional"))
    )
    (net (code "4") (name "GND") (class "Default")
      (node (ref "C3") (pin "2") (pinfunction "2_2") (pintype "passive"))
      (node (ref "C4") (pin "2") (pinfunction "-_2") (pintype "passive"))
      (node (ref "C6") (pin "2") (pinfunction "2_2") (pintype "passive"))
      (node (ref "D1") (pin "C") (pinfunction "C_C") (pintype "passive"))
      (node (ref "P1") (pin "PAD_PD10") (pinfunction "GND4_PAD_PD10") (pintype "power_in"))
      (node (ref "P1") (pin "PAD_PD11") (pinfunction "GND5_PAD_PD11") (pintype "power_in"))
      (node (ref "P1") (pin "PAD_PD8") (pinfunction "GND2_PAD_PD8") (pintype "power_in"))
      (node (ref "P1") (pin "PAD_PD9") (pinfunction "GND3_PAD_PD9") (pintype "power_in"))
      (node (ref "R2") (pin "1") (pinfunction "1_1") (pintype "passive"))
      (node (ref "R3") (pin "1") (pinfunction "1_1") (pintype "passive"))
      (node (ref "U1") (pin "30") (pinfunction "VSS_30") (pintype "passive"))
      (node (ref "U1") (pin "49") (pinfunction "EPAD_49") (pintype "passive"))
      (node (ref "X1") (pin "P$2") (pinfunction "2_P$2") (pintype "passive"))
    )
    (net (code "5") (name "Net-(CT-Pad1)") (class "Default")
      (node (ref "CT") (pin "1") (pinfunction "1_1") (pintype "power_in"))
      (node (ref "D2") (pin "2") (pinfunction "2_2") (pintype "bidirectional"))
      (node (ref "FB2") (pin "2") (pinfunction "2_2") (pintype "passive"))
      (node (ref "R6") (pin "1") (pinfunction "1_1") (pintype "passive"))
    )
    (net (code "6") (name "Net-(CT-Pad2)") (class "Default")
      (node (ref "CT") (pin "2") (pinfunction "2_2") (pintype "power_in"))
      (node (ref "D2") (pin "1") (pinfunction "1_1") (pintype "bidirectional"))
      (node (ref "FB3") (pin "2") (pinfunction "2_2") (pintype "passive"))
      (node (ref "R6") (pin "2") (pinfunction "2_2") (pintype "passive"))
    )
    (net (code "7") (name "Net-(D1-PadA)") (class "Default")
      (node (ref "D1") (pin "A") (pinfunction "A_A") (pintype "passive"))
      (node (ref "R1") (pin "1") (pinfunction "1_1") (pintype "passive"))
    )
    (net (code "8") (name "Net-(D3-Pad1)") (class "Default")
      (node (ref "D3") (pin "1") (pinfunction "1_1") (pintype "bidirectional"))
      (node (ref "FB5") (pin "1") (pinfunction "1_1") (pintype "passive"))
      (node (ref "R14") (pin "1") (pinfunction "1_1") (pintype "passive"))
      (node (ref "R9") (pin "1") (pinfunction "1_1") (pintype "passive"))
    )
    (net (code "9") (name "Net-(D3-Pad2)") (class "Default")
      (node (ref "D3") (pin "2") (pinfunction "2_2") (pintype "bidirectional"))
      (node (ref "FB4") (pin "1") (pinfunction "1_1") (pintype "passive"))
      (node (ref "R10") (pin "1") (pinfunction "1_1") (pintype "passive"))
      (node (ref "R14") (pin "2") (pinfunction "2_2") (pintype "passive"))
    )
    (net (code "10") (name "Net-(FB2-Pad1)") (class "Default")
      (node (ref "FB2") (pin "1") (pinfunction "1_1") (pintype "passive"))
      (node (ref "R4") (pin "1") (pinfunction "1_1") (pintype "passive"))
    )
    (net (code "11") (name "Net-(FB3-Pad1)") (class "Default")
      (node (ref "FB3") (pin "1") (pinfunction "1_1") (pintype "passive"))
      (node (ref "R5") (pin "1") (pinfunction "1_1") (pintype "passive"))
    )
    (net (code "12") (name "Net-(FB4-Pad2)") (class "Default")
      (node (ref "FB4") (pin "2") (pinfunction "2_2") (pintype "passive"))
      (node (ref "R11") (pin "1") (pinfunction "1_1") (pintype "passive"))
    )
    (net (code "13") (name "Net-(FB5-Pad2)") (class "Default")
      (node (ref "FB5") (pin "2") (pinfunction "2_2") (pintype "passive"))
      (node (ref "R12") (pin "1") (pinfunction "1_1") (pintype "passive"))
    )
    (net (code "14") (name "Net-(R8-Pad2)") (class "Default")
      (node (ref "R8") (pin "2") (pinfunction "2_2") (pintype "passive"))
      (node (ref "VIN") (pin "2") (pinfunction "2_2") (pintype "power_in"))
    )
    (net (code "15") (name "Net-(R10-Pad2)") (class "Default")
      (node (ref "R10") (pin "2") (pinfunction "2_2") (pintype "passive"))
      (node (ref "R8") (pin "1") (pinfunction "1_1") (pintype "passive"))
    )
    (net (code "16") (name "Net-(R16-Pad1)") (class "Default")
      (node (ref "R16") (pin "1") (pinfunction "1_1") (pintype "passive"))
      (node (ref "R9") (pin "2") (pinfunction "2_2") (pintype "passive"))
    )
    (net (code "17") (name "Net-(R16-Pad2)") (class "Default")
      (node (ref "R16") (pin "2") (pinfunction "2_2") (pintype "passive"))
      (node (ref "VIN") (pin "1") (pinfunction "1_1") (pintype "power_in"))
    )
    (net (code "18") (name "Net-(U1-PA15)") (class "Default")
      (node (ref "R1") (pin "2") (pinfunction "2_2") (pintype "passive"))
      (node (ref "U1") (pin "37") (pinfunction "PA15_37") (pintype "bidirectional"))
    )
    (net (code "19") (name "Net-(U1-PF0-OSC_IN)") (class "Default")
      (node (ref "U1") (pin "8") (pinfunction "PF0-OSC_IN_8") (pintype "bidirectional"))
      (node (ref "X1") (pin "P$1") (pinfunction "1_P$1") (pintype "passive"))
    )
    (net (code "20") (name "Net-(U1-PF1-OSC_OUT)") (class "Default")
      (node (ref "U1") (pin "9") (pinfunction "PF1-OSC_OUT_9") (pintype "bidirectional"))
      (node (ref "X1") (pin "P$3") (pinfunction "3_P$3") (pintype "passive"))
    )
    (net (code "21") (name "Net-(U1-PF2-NRST)") (class "Default")
      (node (ref "C3") (pin "1") (pinfunction "1_1") (pintype "passive"))
      (node (ref "RESET") (pin "1") (pinfunction "1_1") (pintype "passive"))
      (node (ref "U1") (pin "10") (pinfunction "PF2-NRST_10") (pintype "bidirectional"))
    )
    (net (code "22") (name "Net-(U2-IN+)") (class "Default")
      (node (ref "C10") (pin "2") (pinfunction "2_2") (pintype "passive"))
      (node (ref "C12") (pin "1") (pinfunction "1_1") (pintype "passive"))
      (node (ref "R5") (pin "2") (pinfunction "2_2") (pintype "passive"))
      (node (ref "U2") (pin "4") (pinfunction "IN+_4") (pintype "input"))
    )
    (net (code "23") (name "Net-(U2-IN-)") (class "Default")
      (node (ref "C10") (pin "1") (pinfunction "1_1") (pintype "passive"))
      (node (ref "C11") (pin "2") (pinfunction "2_2") (pintype "passive"))
      (node (ref "R4") (pin "2") (pinfunction "2_2") (pintype "passive"))
      (node (ref "U2") (pin "5") (pinfunction "IN-_5") (pintype "input"))
    )
    (net (code "24") (name "Net-(U2-OUT)") (class "Default")
      (node (ref "R7") (pin "1") (pinfunction "1_1") (pintype "passive"))
      (node (ref "U2") (pin "6") (pinfunction "OUT_6") (pintype "output"))
    )
    (net (code "25") (name "Net-(U3-IN+)") (class "Default")
      (node (ref "C16") (pin "1") (pinfunction "1_1") (pintype "passive"))
      (node (ref "C17") (pin "2") (pinfunction "2_2") (pintype "passive"))
      (node (ref "R11") (pin "2") (pinfunction "2_2") (pintype "passive"))
      (node (ref "U3") (pin "4") (pinfunction "IN+_4") (pintype "input"))
    )
    (net (code "26") (name "Net-(U3-IN-)") (class "Default")
      (node (ref "C16") (pin "2") (pinfunction "2_2") (pintype "passive"))
      (node (ref "C18") (pin "1") (pinfunction "1_1") (pintype "passive"))
      (node (ref "R12") (pin "2") (pinfunction "2_2") (pintype "passive"))
      (node (ref "U3") (pin "5") (pinfunction "IN-_5") (pintype "input"))
    )
    (net (code "27") (name "Net-(U3-OUT)") (class "Default")
      (node (ref "R13") (pin "1") (pinfunction "1_1") (pintype "passive"))
      (node (ref "U3") (pin "6") (pinfunction "OUT_6") (pintype "output"))
    )
    (net (code "28") (name "Net-(U4-EN)") (class "Default")
      (node (ref "C22") (pin "1") (pinfunction "1_1") (pintype "passive"))
      (node (ref "R15") (pin "1") (pinfunction "1_1") (pintype "passive"))
      (node (ref "U4") (pin "3") (pinfunction "EN_3") (pintype "input"))
    )
    (net (code "29") (name "USART1*_RX") (class "Default")
      (node (ref "P1") (pin "PAD_PD4") (pinfunction "SD4_PAD_PD4") (pintype "bidirectional"))
      (node (ref "U1") (pin "32") (pinfunction "PA10_32") (pintype "bidirectional"))
    )
    (net (code "30") (name "USART1*_TX") (class "Default")
      (node (ref "P1") (pin "PAD_PU4") (pinfunction "SU4_PAD_PU4") (pintype "bidirectional"))
      (node (ref "U1") (pin "29") (pinfunction "PA9_29") (pintype "bidirectional"))
    )
    (net (code "31") (name "USART2*_RX") (class "Default")
      (node (ref "P1") (pin "PAD_PD2") (pinfunction "SD2_PAD_PD2") (pintype "bidirectional"))
      (node (ref "U1") (pin "14") (pinfunction "PA3_14") (pintype "bidirectional"))
    )
    (net (code "32") (name "USART2*_TX") (class "Default")
      (node (ref "P1") (pin "PAD_PU2") (pinfunction "SU2_PAD_PU2") (pintype "bidirectional"))
      (node (ref "U1") (pin "13") (pinfunction "PA2_13") (pintype "bidirectional"))
    )
    (net (code "33") (name "USART6_RX") (class "Default")
      (node (ref "P1") (pin "PAD_PD3") (pinfunction "SD3_PAD_PD3") (pintype "bidirectional"))
      (node (ref "U1") (pin "16") (pinfunction "PA5_16") (pintype "bidirectional"))
    )
    (net (code "34") (name "USART6_TX") (class "Default")
      (node (ref "P1") (pin "PAD_PU3") (pinfunction "SU3_PAD_PU3") (pintype "bidirectional"))
      (node (ref "U1") (pin "15") (pinfunction "PA4_15") (pintype "bidirectional"))
    )
    (net (code "35") (name "VBAIS") (class "Default")
      (node (ref "C23") (pin "1") (pinfunction "1_1") (pintype "passive"))
      (node (ref "U2") (pin "1") (pinfunction "REF_1") (pintype "input"))
      (node (ref "U3") (pin "1") (pinfunction "REF_1") (pintype "input"))
      (node (ref "U4") (pin "1") (pinfunction "VBIAS_1") (pintype "power_in"))
    )
    (net (code "36") (name "VBAT") (class "Default")
      (node (ref "U1") (pin "4") (pinfunction "VBAT_4") (pintype "power_in"))
    )
    (net (code "37") (name "VDD") (class "Default")
      (node (ref "C4") (pin "1") (pinfunction "+_1") (pintype "passive"))
      (node (ref "C6") (pin "1") (pinfunction "1_1") (pintype "passive"))
      (node (ref "FB1") (pin "2") (pinfunction "2_2") (pintype "passive"))
      (node (ref "P1") (pin "PAD_PU10") (pinfunction "VDD4_PAD_PU10") (pintype "power_in"))
      (node (ref "P1") (pin "PAD_PU11") (pinfunction "VDD5_PAD_PU11") (pintype "power_in"))
      (node (ref "P1") (pin "PAD_PU8") (pinfunction "VDD2_PAD_PU8") (pintype "power_in"))
      (node (ref "P1") (pin "PAD_PU9") (pinfunction "VDD3_PAD_PU9") (pintype "power_in"))
      (node (ref "U1") (pin "31") (pinfunction "VDDIO2_31") (pintype "power_in"))
    )
    (net (code "38") (name "VDDA") (class "Default")
      (node (ref "C1") (pin "1") (pinfunction "+_1") (pintype "passive"))
      (node (ref "C13") (pin "1") (pinfunction "1_1") (pintype "passive"))
      (node (ref "C14") (pin "1") (pinfunction "1_1") (pintype "passive"))
      (node (ref "C21") (pin "1") (pinfunction "1_1") (pintype "passive"))
      (node (ref "C24") (pin "1") (pinfunction "+_1") (pintype "passive"))
      (node (ref "C7") (pin "1") (pinfunction "+_1") (pintype "passive"))
      (node (ref "C8") (pin "1") (pinfunction "1_1") (pintype "passive"))
      (node (ref "C9") (pin "1") (pinfunction "+_1") (pintype "passive"))
      (node (ref "FB1") (pin "1") (pinfunction "1_1") (pintype "passive"))
      (node (ref "R15") (pin "2") (pinfunction "2_2") (pintype "passive"))
      (node (ref "U1") (pin "6") (pinfunction "VDD/VDDA_6") (pintype "power_in"))
      (node (ref "U2") (pin "3") (pinfunction "V+_3") (pintype "power_in"))
      (node (ref "U3") (pin "3") (pinfunction "V+_3") (pintype "power_in"))
      (node (ref "U4") (pin "4") (pinfunction "VIN_4") (pintype "power_in"))
    )
    (net (code "39") (name "VOLTAGE_SENSE") (class "Default")
      (node (ref "C19") (pin "1") (pinfunction "1_1") (pintype "passive"))
      (node (ref "R13") (pin "2") (pinfunction "2_2") (pintype "passive"))
      (node (ref "U1") (pin "24") (pinfunction "PB12_24") (pintype "bidirectional"))
    )
    (net (code "40") (name "VREF") (class "Default")
      (node (ref "C2") (pin "1") (pinfunction "+_1") (pintype "passive"))
      (node (ref "C20") (pin "1") (pinfunction "1_1") (pintype "passive"))
      (node (ref "C5") (pin "1") (pinfunction "1_1") (pintype "passive"))
      (node (ref "U1") (pin "5") (pinfunction "VREF+_5") (pintype "power_in"))
      (node (ref "U4") (pin "5") (pinfunction "VREF_5") (pintype "power_in"))
    )
    (net (code "41") (name "VSSA") (class "Default")
      (node (ref "C1") (pin "2") (pinfunction "-_2") (pintype "passive"))
      (node (ref "C11") (pin "1") (pinfunction "1_1") (pintype "passive"))
      (node (ref "C12") (pin "2") (pinfunction "2_2") (pintype "passive"))
      (node (ref "C13") (pin "2") (pinfunction "2_2") (pintype "passive"))
      (node (ref "C14") (pin "2") (pinfunction "2_2") (pintype "passive"))
      (node (ref "C15") (pin "2") (pinfunction "2_2") (pintype "passive"))
      (node (ref "C17") (pin "1") (pinfunction "1_1") (pintype "passive"))
      (node (ref "C18") (pin "2") (pinfunction "2_2") (pintype "passive"))
      (node (ref "C19") (pin "2") (pinfunction "2_2") (pintype "passive"))
      (node (ref "C2") (pin "2") (pinfunction "-_2") (pintype "passive"))
      (node (ref "C20") (pin "2") (pinfunction "2_2") (pintype "passive"))
      (node (ref "C21") (pin "2") (pinfunction "2_2") (pintype "passive"))
      (node (ref "C22") (pin "2") (pinfunction "2_2") (pintype "passive"))
      (node (ref "C23") (pin "2") (pinfunction "2_2") (pintype "passive"))
      (node (ref "C24") (pin "2") (pinfunction "-_2") (pintype "passive"))
      (node (ref "C5") (pin "2") (pinfunction "2_2") (pintype "passive"))
      (node (ref "C7") (pin "2") (pinfunction "-_2") (pintype "passive"))
      (node (ref "C8") (pin "2") (pinfunction "2_2") (pintype "passive"))
      (node (ref "C9") (pin "2") (pinfunction "-_2") (pintype "passive"))
      (node (ref "R2") (pin "2") (pinfunction "2_2") (pintype "passive"))
      (node (ref "U1") (pin "7") (pinfunction "VSS/VSSA_7") (pintype "passive"))
      (node (ref "U2") (pin "2") (pinfunction "GND_2") (pintype "passive"))
      (node (ref "U3") (pin "2") (pinfunction "GND_2") (pintype "passive"))
      (node (ref "U4") (pin "2") (pinfunction "GND_2") (pintype "power_in"))
    )
    (net (code "42") (name "unconnected-(U1-PA0-Pad11)") (class "Default")
      (node (ref "U1") (pin "11") (pinfunction "PA0_11") (pintype "bidirectional"))
    )
    (net (code "43") (name "unconnected-(U1-PA1-Pad12)") (class "Default")
      (node (ref "U1") (pin "12") (pinfunction "PA1_12") (pintype "bidirectional"))
    )
    (net (code "44") (name "unconnected-(U1-PA7-Pad18)") (class "Default")
      (node (ref "U1") (pin "18") (pinfunction "PA7_18") (pintype "bidirectional"))
    )
    (net (code "45") (name "unconnected-(U1-PA8-Pad28)") (class "Default")
      (node (ref "U1") (pin "28") (pinfunction "PA8_28") (pintype "bidirectional"))
    )
    (net (code "46") (name "unconnected-(U1-PA11[PA9]-Pad33)") (class "Default")
      (node (ref "U1") (pin "33") (pinfunction "PA11[PA9]_33") (pintype "bidirectional"))
    )
    (net (code "47") (name "unconnected-(U1-PA12[PA10]-Pad34)") (class "Default")
      (node (ref "U1") (pin "34") (pinfunction "PA12[PA10]_34") (pintype "bidirectional"))
    )
    (net (code "48") (name "unconnected-(U1-PB0-Pad19)") (class "Default")
      (node (ref "U1") (pin "19") (pinfunction "PB0_19") (pintype "bidirectional"))
    )
    (net (code "49") (name "unconnected-(U1-PB1-Pad20)") (class "Default")
      (node (ref "U1") (pin "20") (pinfunction "PB1_20") (pintype "bidirectional"))
    )
    (net (code "50") (name "unconnected-(U1-PB2-Pad21)") (class "Default")
      (node (ref "U1") (pin "21") (pinfunction "PB2_21") (pintype "bidirectional"))
    )
    (net (code "51") (name "unconnected-(U1-PB3-Pad42)") (class "Default")
      (node (ref "U1") (pin "42") (pinfunction "PB3_42") (pintype "bidirectional"))
    )
    (net (code "52") (name "unconnected-(U1-PB4-Pad43)") (class "Default")
      (node (ref "U1") (pin "43") (pinfunction "PB4_43") (pintype "bidirectional"))
    )
    (net (code "53") (name "unconnected-(U1-PB5-Pad44)") (class "Default")
      (node (ref "U1") (pin "44") (pinfunction "PB5_44") (pintype "bidirectional"))
    )
    (net (code "54") (name "unconnected-(U1-PB6-Pad45)") (class "Default")
      (node (ref "U1") (pin "45") (pinfunction "PB6_45") (pintype "bidirectional"))
    )
    (net (code "55") (name "unconnected-(U1-PB7-Pad46)") (class "Default")
      (node (ref "U1") (pin "46") (pinfunction "PB7_46") (pintype "bidirectional"))
    )
    (net (code "56") (name "unconnected-(U1-PB8-Pad47)") (class "Default")
      (node (ref "U1") (pin "47") (pinfunction "PB8_47") (pintype "bidirectional"))
    )
    (net (code "57") (name "unconnected-(U1-PB9-Pad48)") (class "Default")
      (node (ref "U1") (pin "48") (pinfunction "PB9_48") (pintype "bidirectional"))
    )
    (net (code "58") (name "unconnected-(U1-PB10-Pad22)") (class "Default")
      (node (ref "U1") (pin "22") (pinfunction "PB10_22") (pintype "bidirectional"))
    )
    (net (code "59") (name "unconnected-(U1-PB11-Pad23)") (class "Default")
      (node (ref "U1") (pin "23") (pinfunction "PB11_23") (pintype "bidirectional"))
    )
    (net (code "60") (name "unconnected-(U1-PB13-Pad25)") (class "Default")
      (node (ref "U1") (pin "25") (pinfunction "PB13_25") (pintype "bidirectional"))
    )
    (net (code "61") (name "unconnected-(U1-PB14-Pad26)") (class "Default")
      (node (ref "U1") (pin "26") (pinfunction "PB14_26") (pintype "bidirectional"))
    )
    (net (code "62") (name "unconnected-(U1-PB15-Pad27)") (class "Default")
      (node (ref "U1") (pin "27") (pinfunction "PB15_27") (pintype "bidirectional"))
    )
    (net (code "63") (name "unconnected-(U1-PC13-Pad1)") (class "Default")
      (node (ref "U1") (pin "1") (pinfunction "PC13_1") (pintype "bidirectional"))
    )
    (net (code "64") (name "unconnected-(U1-PC14-OSC32_IN-Pad2)") (class "Default")
      (node (ref "U1") (pin "2") (pinfunction "PC14-OSC32_IN_2") (pintype "bidirectional"))
    )
    (net (code "65") (name "unconnected-(U1-PC15-OSC32_OUT-Pad3)") (class "Default")
      (node (ref "U1") (pin "3") (pinfunction "PC15-OSC32_OUT_3") (pintype "bidirectional"))
    )
    (net (code "66") (name "unconnected-(U1-PD0-Pad38)") (class "Default")
      (node (ref "U1") (pin "38") (pinfunction "PD0_38") (pintype "bidirectional"))
    )
    (net (code "67") (name "unconnected-(U1-PD1-Pad39)") (class "Default")
      (node (ref "U1") (pin "39") (pinfunction "PD1_39") (pintype "bidirectional"))
    )
    (net (code "68") (name "unconnected-(U1-PD2-Pad40)") (class "Default")
      (node (ref "U1") (pin "40") (pinfunction "PD2_40") (pintype "bidirectional"))
    )
    (net (code "69") (name "unconnected-(U1-PD3-Pad41)") (class "Default")
      (node (ref "U1") (pin "41") (pinfunction "PD3_41") (pintype "bidirectional"))
    )
  )
)
